# CC2640R2.net
KiCad netlist of a schematic drawn in Altium Designer
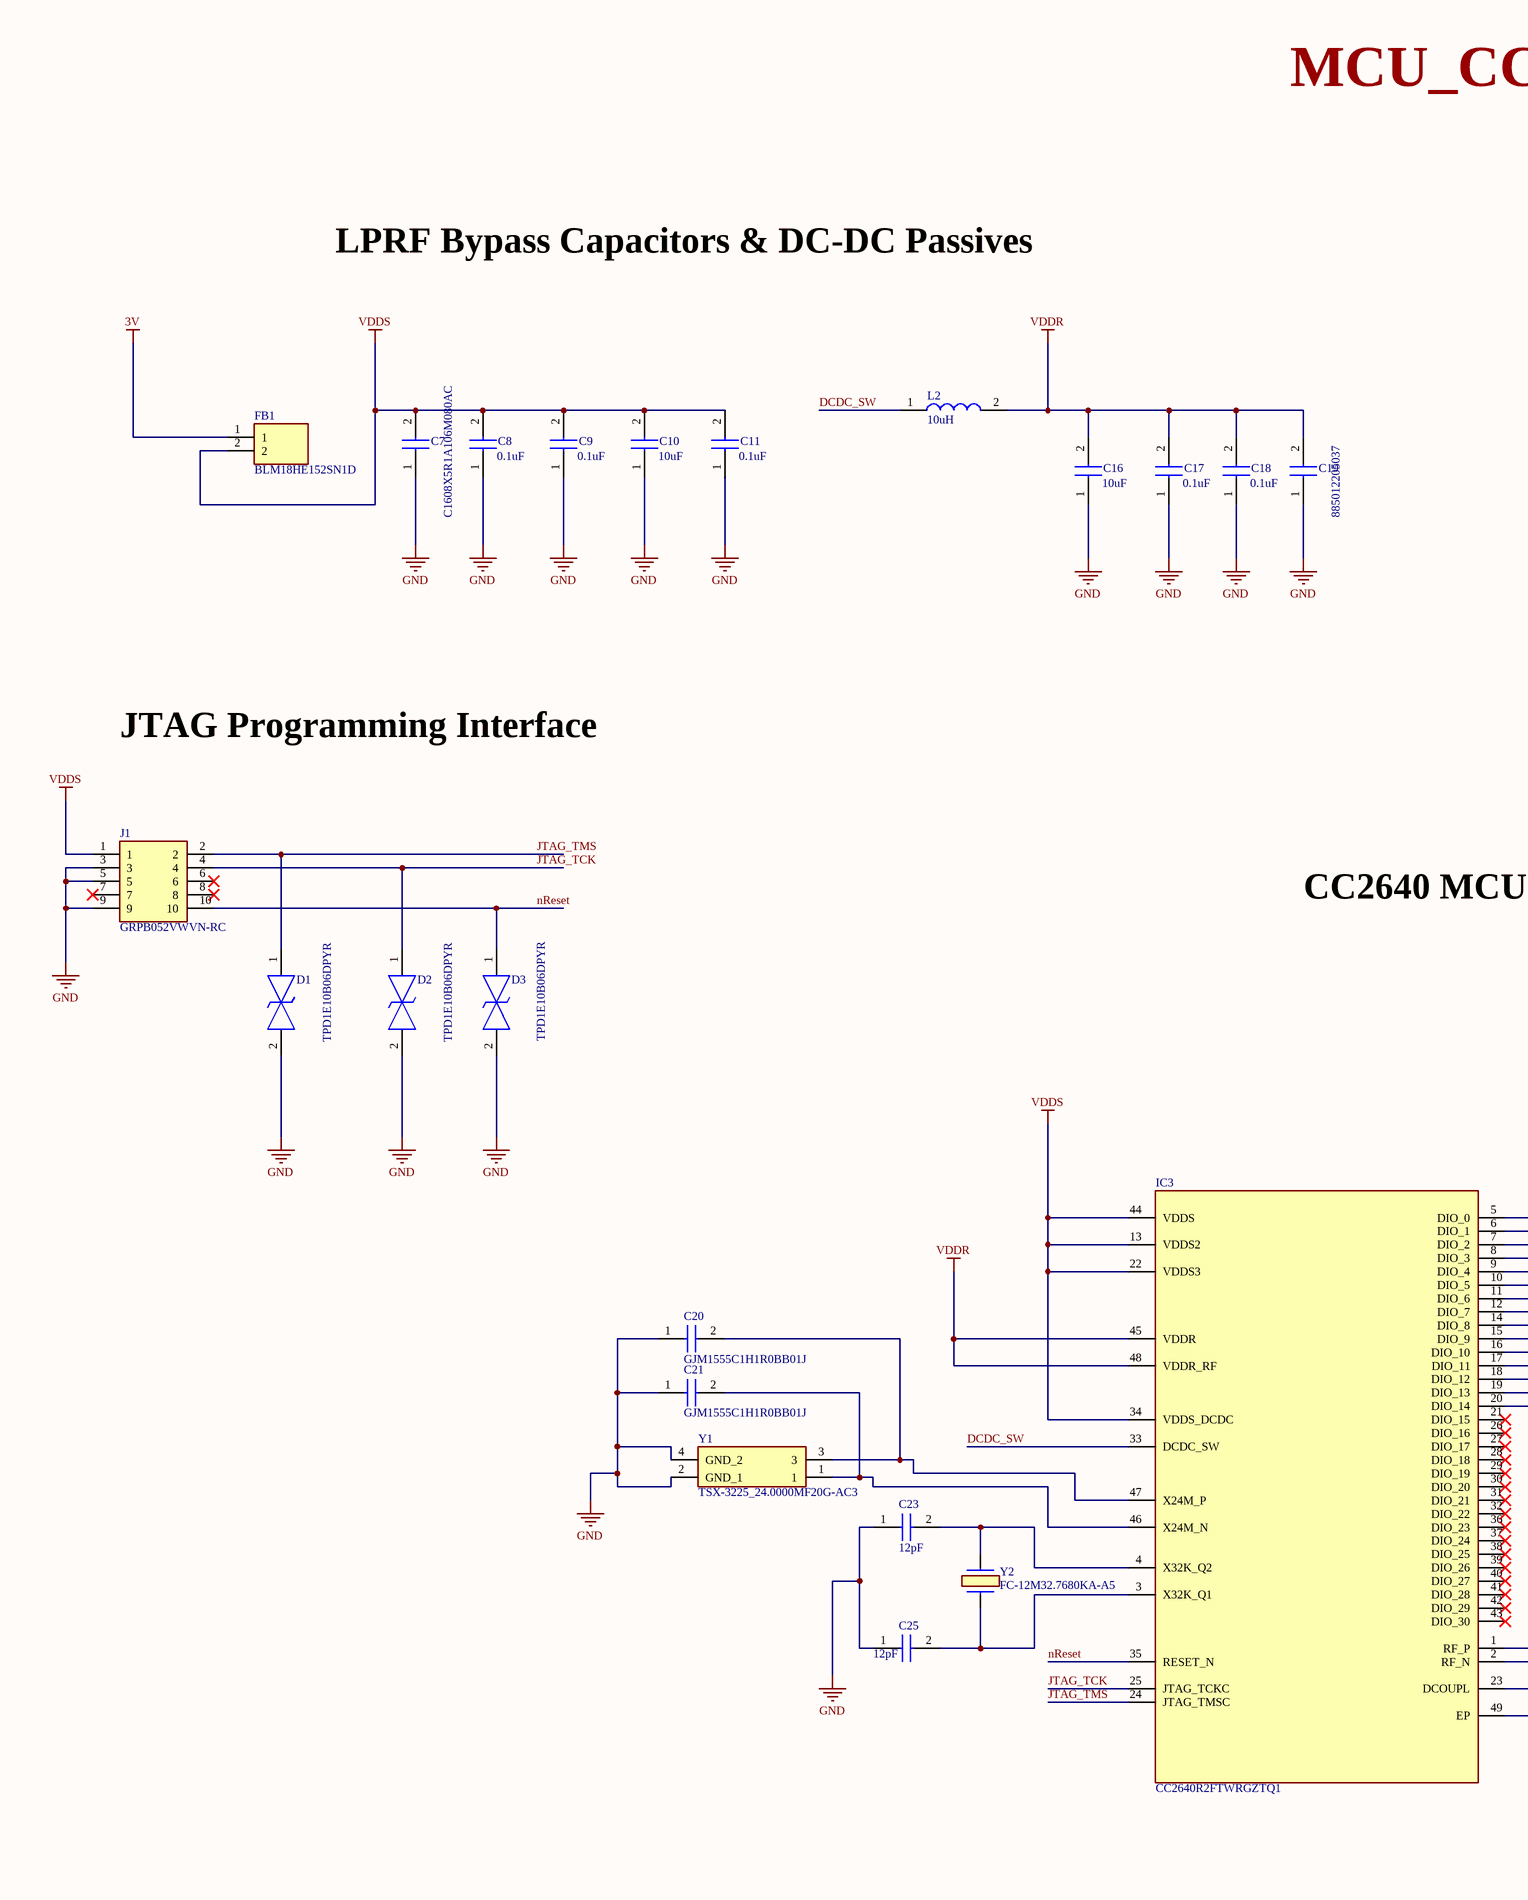
[diagram p0: CC2640R2.SchDoc, left]
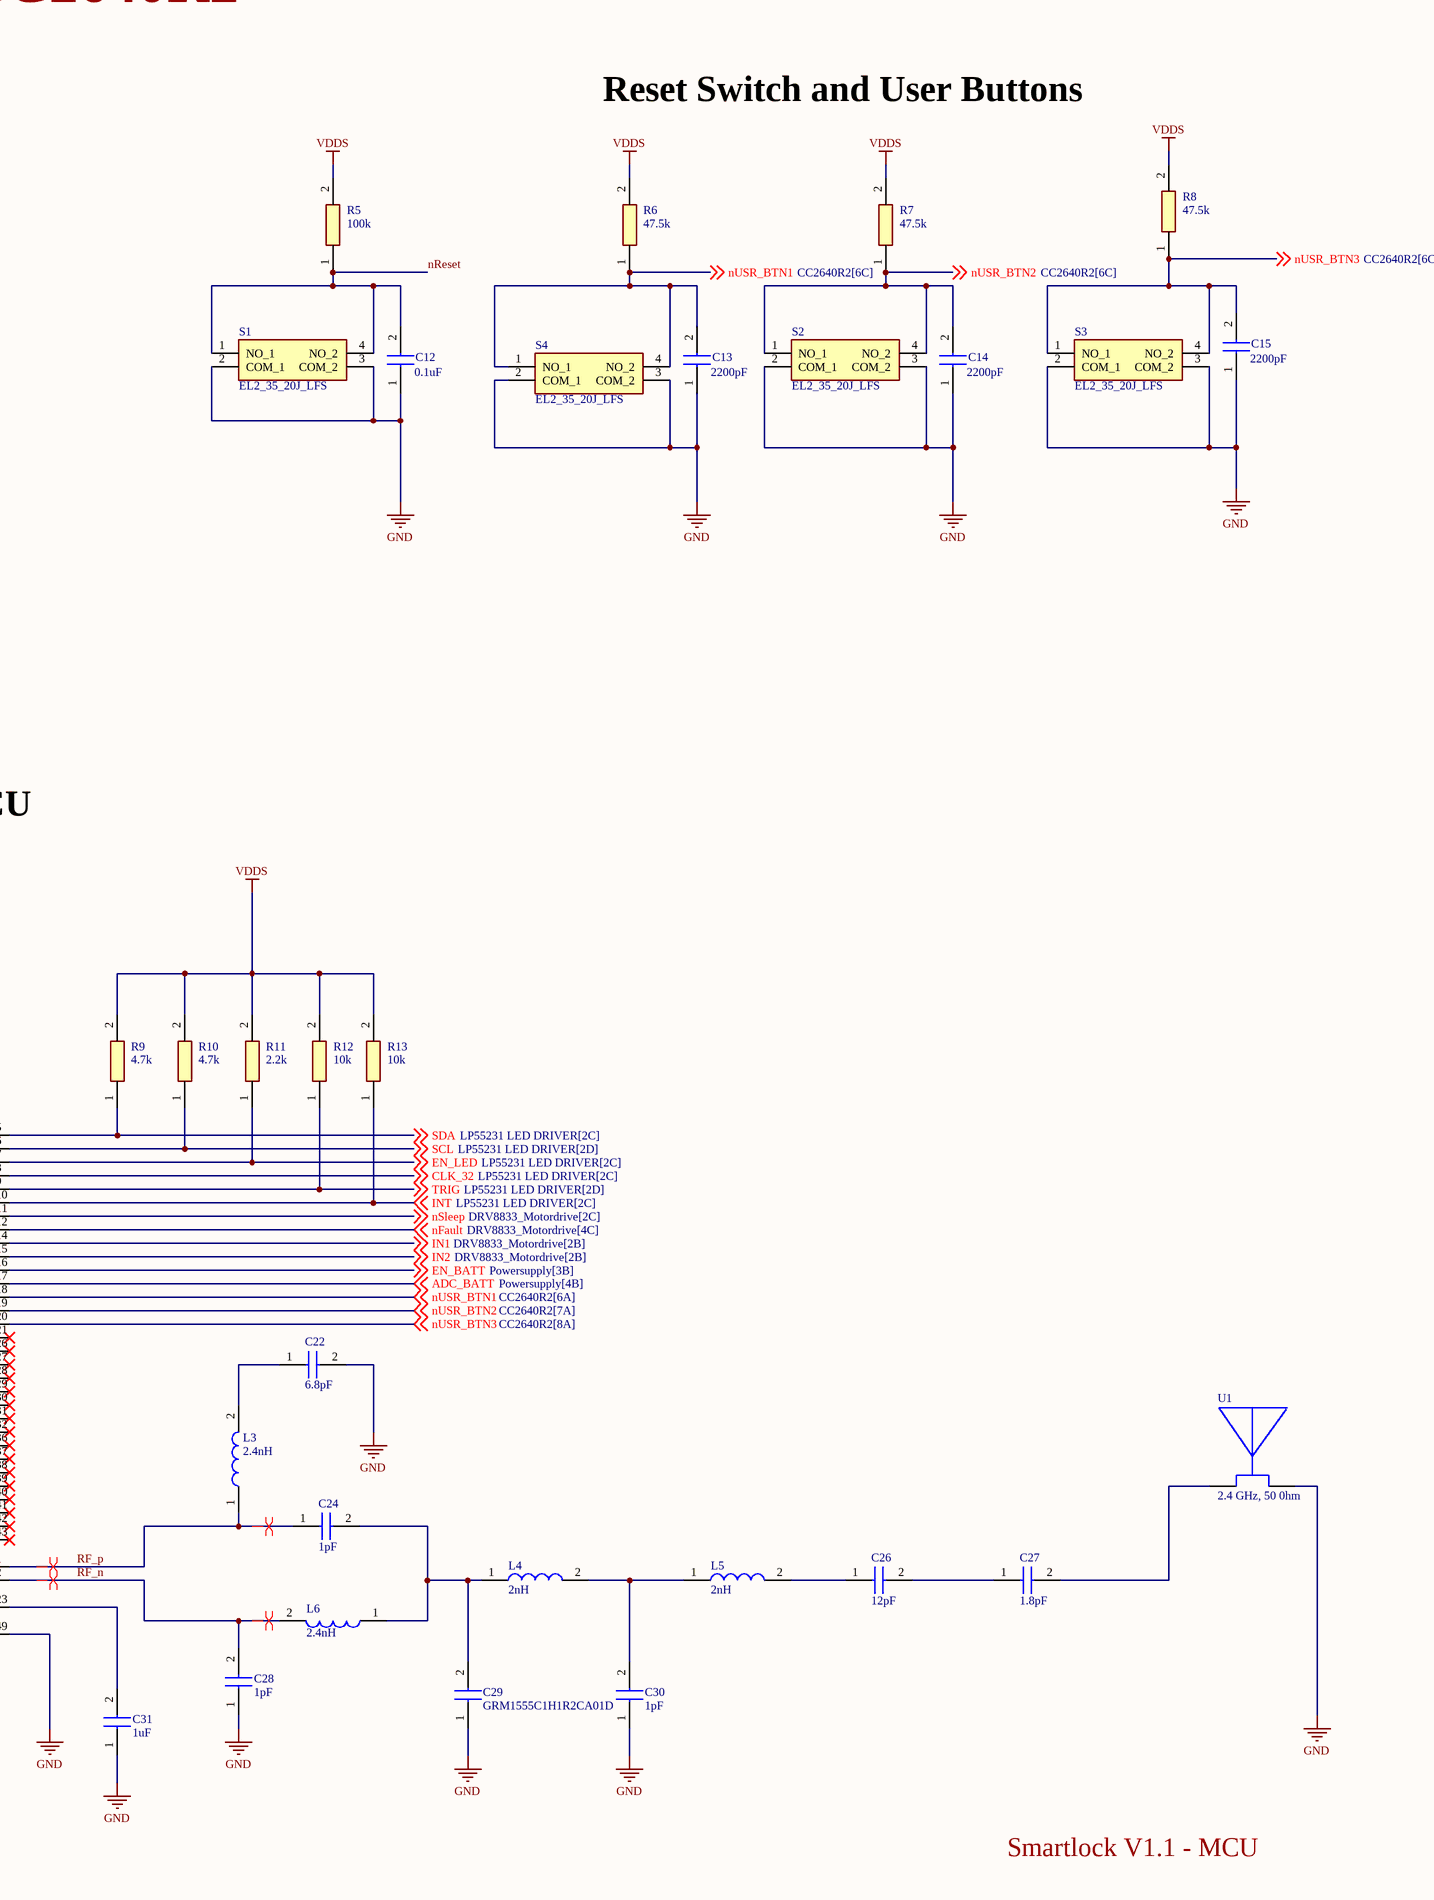
[diagram p1: CC2640R2.SchDoc, right]

(export (version "E")
  (design (tool "Eeschema 10.0.6"))
  (components
    (comp (ref "C7")
      (value "C1608X5R1A106M080AC")
      (footprint "Smart_lockV1.1:CAPC1608X80N")
      (description "Capacitor")
      (fields (field (name "MOUSER PART NUMBER") "810-C1608X5R1A106M"))
      (libsource (lib "*") (part "C1608X5R1A106M080AC"))
    )
    (comp (ref "C8")
      (value "0.1uF")
      (footprint "Smart_lockV1.1:CAPC1005X55N")
      (description "Capacitor,0.1uF 10V X7R")
      (fields
        (field (name "MANUFACTURER_PART_NUMBER") "GRM155R71A104KA01D")
        (field (name "MOUSER PART NUMBER") "81-GRM155R71A104KA1D")
      )
      (libsource (lib "*") (part "GRM155R71A104KA01D"))
    )
    (comp (ref "C9")
      (value "0.1uF")
      (footprint "Smart_lockV1.1:CAPC1005X55N")
      (description "Capacitor,0.1uF 10V X7R")
      (fields
        (field (name "MANUFACTURER_PART_NUMBER") "GRM155R71A104KA01D")
        (field (name "MOUSER PART NUMBER") "81-GRM155R71A104KA1D")
      )
      (libsource (lib "*") (part "GRM155R71A104KA01D"))
    )
    (comp (ref "C10")
      (value "10uF")
      (footprint "Smart_lockV1.1:CAPC2012X145N")
      (description "Capacitor,10uF 10V X7R")
      (fields
        (field (name "MANUFACTURER_PART_NUMBER") "GRM21BR71A106KE51L")
        (field (name "MOUSER PART NUMBER") "81-GRM21BR71A106KE51")
      )
      (libsource (lib "*") (part "GRM21BR71A106KE51L"))
    )
    (comp (ref "C11")
      (value "0.1uF")
      (footprint "Smart_lockV1.1:CAPC1005X55N")
      (description "Capacitor,01uF 10V X7R")
      (fields
        (field (name "MANUFACTURER_PART_NUMBER") "GRM155R71A104KA01D")
        (field (name "MOUSER PART NUMBER") "81-GRM155R71A104KA1D")
      )
      (libsource (lib "*") (part "GRM155R71A104KA01D"))
    )
    (comp (ref "C12")
      (value "0.1uF")
      (footprint "Smart_lockV1.1:CAPC1005X55N")
      (description "Capacitor 0.1uF 25V")
      (fields
        (field (name "MANUFACTURER_PART_NUMBER") "CGA2B3X7R1E104K050BB")
        (field (name "MOUSER PART NUMBER") "810-CGA2B3X7R1E104K")
      )
      (libsource (lib "*") (part "CGA2B3X7R1E104K050BB"))
    )
    (comp (ref "C13")
      (value "2200pF")
      (footprint "Smart_lockV1.1:CAPC1005X55N")
      (description "Capacitor 2200pF 50V")
      (fields
        (field (name "MANUFACTURER_PART_NUMBER") "C1005X7R1H222K050BA")
        (field (name "MOUSER PART NUMBER") "810-C1005X7R1H222K")
      )
      (libsource (lib "*") (part "C1005X7R1H222K050BA"))
    )
    (comp (ref "C14")
      (value "2200pF")
      (footprint "Smart_lockV1.1:CAPC1005X55N")
      (description "Capacitor")
      (fields
        (field (name "MANUFACTURER_PART_NUMBER") "C1005X7R1H222K050BA")
        (field (name "MOUSER PART NUMBER") "810-C1005X7R1H222K")
      )
      (libsource (lib "*") (part "C1005X7R1H222K050BA"))
    )
    (comp (ref "C15")
      (value "2200pF")
      (footprint "Smart_lockV1.1:CAPC1005X55N")
      (description "Capacitor")
      (fields
        (field (name "MANUFACTURER_PART_NUMBER") "C1005X7R1H222K050BA")
        (field (name "MOUSER PART NUMBER") "810-C1005X7R1H222K")
      )
      (libsource (lib "*") (part "C1005X7R1H222K050BA"))
    )
    (comp (ref "C16")
      (value "10uF")
      (footprint "Smart_lockV1.1:CAPC2012X145N")
      (description "Capacitor 10uF 10V X7R")
      (fields
        (field (name "MANUFACTURER_PART_NUMBER") "GRM21BR71A106KE51L")
        (field (name "MOUSER PART NUMBER") "81-GRM21BR71A106KE51")
      )
      (libsource (lib "*") (part "GRM21BR71A106KE51L"))
    )
    (comp (ref "C17")
      (value "0.1uF")
      (footprint "Smart_lockV1.1:CAPC1005X55N")
      (description "Capacitor 0.1uF 10V X7R")
      (fields
        (field (name "MANUFACTURER_PART_NUMBER") "GRM155R71A104KA01D")
        (field (name "MOUSER PART NUMBER") "81-GRM155R71A104KA1D")
      )
      (libsource (lib "*") (part "GRM155R71A104KA01D"))
    )
    (comp (ref "C18")
      (value "0.1uF")
      (footprint "Smart_lockV1.1:CAPC1005X55N")
      (description "Capacitor 0.1uF 10V X7R")
      (fields
        (field (name "MANUFACTURER_PART_NUMBER") "GRM155R71A104KA01D")
        (field (name "MOUSER PART NUMBER") "81-GRM155R71A104KA1D")
      )
      (libsource (lib "*") (part "GRM155R71A104KA01D"))
    )
    (comp (ref "C19")
      (value "885012205037")
      (footprint "Smart_lockV1.1:CAPC1005X55N")
      (description "Capacitor")
      (fields (field (name "MOUSER PART NUMBER") "710-885012205037"))
      (libsource (lib "*") (part "885012205037"))
    )
    (comp (ref "C20")
      (value "GJM1555C1H1R0BB01J")
      (footprint "Smart_lockV1.1:CAPC1005X55N")
      (description "Capacitor")
      (fields (field (name "MOUSER PART NUMBER") "81-GJM1555C1H1R0BB1J"))
      (libsource (lib "*") (part "GJM1555C1H1R0BB01J"))
    )
    (comp (ref "C21")
      (value "GJM1555C1H1R0BB01J")
      (footprint "Smart_lockV1.1:CAPC1005X55N")
      (description "Capacitor")
      (fields (field (name "MOUSER PART NUMBER") "81-GJM1555C1H1R0BB1J"))
      (libsource (lib "*") (part "GJM1555C1H1R0BB01J"))
    )
    (comp (ref "C22")
      (value "6.8pF")
      (footprint "Smart_lockV1.1:CAPC1005X55N")
      (description "6.8pF Capacitor 50V")
      (fields
        (field (name "MANUFACTURER_PART_NUMBER") "GRM1555C1H6R8CA01D")
        (field (name "MOUSER PART NUMBER") "81-GRM1555C1H6R8CA1D")
      )
      (libsource (lib "*") (part "GRM1555C1H6R8CA01D"))
    )
    (comp (ref "C23")
      (value "12pF")
      (footprint "Smart_lockV1.1:CAPC1005X55N")
      (description "Capacitor 12pF 50V")
      (fields
        (field (name "MANUFACTURER_PART_NUMBER") "GRM1555C1H120JA01D")
        (field (name "MOUSER PART NUMBER") "81-GRM1555C1H120JA1D")
      )
      (libsource (lib "*") (part "GRM1555C1H120JA01D"))
    )
    (comp (ref "C24")
      (value "1pF")
      (footprint "Smart_lockV1.1:CAPC1005X55N")
      (description "Capacitor 1pF 50V")
      (fields
        (field (name "MANUFACTURER_PART_NUMBER") "GJM1555C1H1R0BB01J")
        (field (name "MOUSER PART NUMBER") "81-GJM1555C1H1R0BB1J")
      )
      (libsource (lib "*") (part "GJM1555C1H1R0BB01J"))
    )
    (comp (ref "C25")
      (value "12pF")
      (footprint "Smart_lockV1.1:CAPC1005X55N")
      (description "Capacitor 12 pF 50V")
      (fields
        (field (name "MANUFACTURER_PART_NUMBER") "GRM1555C1H120JA01D")
        (field (name "MOUSER PART NUMBER") "81-GRM1555C1H120JA1D")
      )
      (libsource (lib "*") (part "GRM1555C1H120JA01D"))
    )
    (comp (ref "C26")
      (value "12pF")
      (footprint "Smart_lockV1.1:CAPC1005X55N")
      (description "Capacitor")
      (fields
        (field (name "MANUFACTURER_PART_NUMBER") "GRM1555C1H120JA01D")
        (field (name "MOUSER PART NUMBER") "81-GRM1555C1H120JA1D")
      )
      (libsource (lib "*") (part "GRM1555C1H120JA01D"))
    )
    (comp (ref "C27")
      (value "1.8pF")
      (footprint "Smart_lockV1.1:CAPC1005X55N")
      (description "Capacitor")
      (fields
        (field (name "MANUFACTURER_PART_NUMBER") "GRM1555C1H1R8CA01D")
        (field (name "MOUSER PART NUMBER") "81-GRM1555C1H1R8CA1D")
      )
      (libsource (lib "*") (part "GRM1555C1H1R8CA01D"))
    )
    (comp (ref "C28")
      (value "1pF")
      (footprint "Smart_lockV1.1:CAPC1005X55N")
      (description "Capacitor 1pF 5V")
      (fields
        (field (name "MANUFACTURER_PART_NUMBER") "GJM1555C1H1R0BB01J")
        (field (name "MOUSER PART NUMBER") "81-GJM1555C1H1R0BB1J")
      )
      (libsource (lib "*") (part "GJM1555C1H1R0BB01J"))
    )
    (comp (ref "C29")
      (value "GRM1555C1H1R2CA01D")
      (footprint "Smart_lockV1.1:CAPC1005X55N")
      (description "Capacitor")
      (fields (field (name "MOUSER PART NUMBER") "81-GRM1555C1H1R2CA1D"))
      (libsource (lib "*") (part "GRM1555C1H1R2CA01D"))
    )
    (comp (ref "C30")
      (value "1pF")
      (footprint "Smart_lockV1.1:CAPC1005X55N")
      (description "Capacitor 1pF")
      (fields
        (field (name "MANUFACTURER_PART_NUMBER") "GJM1555C1H1R0BB01J")
        (field (name "MOUSER PART NUMBER") "81-GJM1555C1H1R0BB1J")
      )
      (libsource (lib "*") (part "GJM1555C1H1R0BB01J"))
    )
    (comp (ref "C31")
      (value "1uF")
      (footprint "Smart_lockV1.1:CAPC1005X55N")
      (description "Capacitor 1uF 10V X5R")
      (fields
        (field (name "MANUFACTURER_PART_NUMBER") "GRM155R61A105KE15D")
        (field (name "MOUSER PART NUMBER") "81-GRM155R61A105KE15")
      )
      (libsource (lib "*") (part "GRM155R61A105KE15D"))
    )
    (comp (ref "D1")
      (value "TPD1E10B06DPYR")
      (footprint "Smart_lockV1.1:TPD1E10B06DPYR")
      (description "TVS Diode (Bi-directional)")
      (fields (field (name "MOUSER PART NUMBER") "595-TPD1E10B06DPYR"))
      (libsource (lib "*") (part "TPD1E10B06DPYR"))
    )
    (comp (ref "D2")
      (value "TPD1E10B06DPYR")
      (footprint "Smart_lockV1.1:TPD1E10B06DPYR")
      (description "TVS Diode (Bi-directional)")
      (fields (field (name "MOUSER PART NUMBER") "595-TPD1E10B06DPYR"))
      (libsource (lib "*") (part "TPD1E10B06DPYR"))
    )
    (comp (ref "D3")
      (value "TPD1E10B06DPYR")
      (footprint "Smart_lockV1.1:TPD1E10B06DPYR")
      (description "TVS Diode (Bi-directional)")
      (fields (field (name "MOUSER PART NUMBER") "595-TPD1E10B06DPYR"))
      (libsource (lib "*") (part "TPD1E10B06DPYR"))
    )
    (comp (ref "FB1")
      (value "BLM18HE152SN1D")
      (footprint "Smart_lockV1.1:BLM18SP221SN1B")
      (description "Ferrite Bead")
      (fields (field (name "MOUSER PART NUMBER") "81-BLM18HE152SN1D"))
      (libsource (lib "*") (part "BLM18HE152SN1D"))
    )
    (comp (ref "IC3")
      (value "CC2640R2FTWRGZTQ1")
      (footprint "QFN50P700X700X100-49N-D")
      (description "Integrated Circuit")
      (fields (field (name "MOUSER PART NUMBER") "595-2640R2FTWRGZTQ1"))
      (libsource (lib "Smart_lockV1.1") (part "CC2640R2FTWRGZTQ1"))
    )
    (comp (ref "J1")
      (value "GRPB052VWVN-RC")
      (footprint "Smart_lockV1.1:HDRV10W50P127_2X5_635X340X430P")
      (description "Connector")
      (libsource (lib "*") (part "GRPB052VWVN-RC"))
    )
    (comp (ref "L2")
      (value "10uH")
      (footprint "Smart_lockV1.1:INDC2112X145N")
      (description "Inductor,10uH")
      (fields
        (field (name "MANUFACTURER_PART_NUMBER") "CKS2125100M-T")
        (field (name "MOUSER PART NUMBER") "963-CKS2125100M-T")
      )
      (libsource (lib "*") (part "CKS2125100M-T"))
    )
    (comp (ref "L3")
      (value "2.4nH")
      (footprint "Smart_lockV1.1:LQG15WH0N7B02D")
      (description "Inductor 2.4 nH")
      (fields
        (field (name "MANUFACTURER_PART_NUMBER") "LQG15HN2N4S02D")
        (field (name "MOUSER PART NUMBER") "81-LQG15HN2N4S02D")
      )
      (libsource (lib "*") (part "LQG15HN2N4S02D"))
    )
    (comp (ref "L4")
      (value "2nH")
      (footprint "Smart_lockV1.1:LQG15WH0N7B02D")
      (description "Inductor")
      (fields
        (field (name "MANUFACTURER_PART_NUMBER") "LQG15HS2N0S02D")
        (field (name "MOUSER PART NUMBER") "81-LQG15HS2N0S02D")
      )
      (libsource (lib "*") (part "LQG15HS2N0S02D"))
    )
    (comp (ref "L5")
      (value "2nH")
      (footprint "Smart_lockV1.1:LQG15WH0N7B02D")
      (description "Inductor")
      (fields
        (field (name "MANUFACTURER_PART_NUMBER") "LQG15HS2N0S02D")
        (field (name "MOUSER PART NUMBER") "81-LQG15HS2N0S02D")
      )
      (libsource (lib "*") (part "LQG15HS2N0S02D"))
    )
    (comp (ref "L6")
      (value "2.4nH")
      (footprint "Smart_lockV1.1:LQG15WH0N7B02D")
      (description "Inductor")
      (fields
        (field (name "MANUFACTURER_PART_NUMBER") "LQG15HN2N4S02D")
        (field (name "MOUSER PART NUMBER") "81-LQG15HN2N4S02D")
      )
      (libsource (lib "*") (part "LQG15HN2N4S02D"))
    )
    (comp (ref "R5")
      (value "100k")
      (footprint "Smart_lockV1.1:RESC1005X35N")
      (description "Resistor")
      (fields
        (field (name "MANUFACTURER_PART_NUMBER") "RMCF0402FT100K")
        (field (name "MOUSER PART NUMBER") "708-RMCF0402FT100K")
      )
      (libsource (lib "*") (part "RMCF0402FT100K"))
    )
    (comp (ref "R6")
      (value "47.5k")
      (footprint "Smart_lockV1.1:RESC1005X40N")
      (description "Resistor")
      (fields
        (field (name "MANUFACTURER_PART_NUMBER") "CRCW040247K5FKED")
        (field (name "MOUSER PART NUMBER") "71-CRCW0402-47.5K-E3")
      )
      (libsource (lib "*") (part "CRCW040247K5FKED"))
    )
    (comp (ref "R7")
      (value "47.5k")
      (footprint "Smart_lockV1.1:RESC1005X40N")
      (description "Resistor")
      (fields
        (field (name "MANUFACTURER_PART_NUMBER") "CRCW040247K5FKED")
        (field (name "MOUSER PART NUMBER") "71-CRCW0402-47.5K-E3")
      )
      (libsource (lib "*") (part "CRCW040247K5FKED"))
    )
    (comp (ref "R8")
      (value "47.5k")
      (footprint "Smart_lockV1.1:RESC1005X40N")
      (description "Resistor")
      (fields
        (field (name "MANUFACTURER_PART_NUMBER") "CRCW040247K5FKED")
        (field (name "MOUSER PART NUMBER") "71-CRCW0402-47.5K-E3")
      )
      (libsource (lib "*") (part "CRCW040247K5FKED"))
    )
    (comp (ref "R9")
      (value "4.7k")
      (footprint "Smart_lockV1.1:ERJ3EKF1000V")
      (description "Resistor")
      (fields
        (field (name "MANUFACTURER_PART_NUMBER") "ERJ-3GEYJ472V")
        (field (name "MOUSER PART NUMBER") "667-ERJ-3GEYJ472V")
      )
      (libsource (lib "*") (part "ERJ-3GEYJ472V"))
    )
    (comp (ref "R10")
      (value "4.7k")
      (footprint "Smart_lockV1.1:ERJ3EKF1000V")
      (description "Resistor")
      (fields
        (field (name "MANUFACTURER_PART_NUMBER") "ERJ-3GEYJ472V")
        (field (name "MOUSER PART NUMBER") "667-ERJ-3GEYJ472V")
      )
      (libsource (lib "*") (part "ERJ-3GEYJ472V"))
    )
    (comp (ref "R11")
      (value "2.2k")
      (footprint "Smart_lockV1.1:RESC1608X55N")
      (description "Resistor")
      (fields
        (field (name "MANUFACTURER_PART_NUMBER") "RC0603FR-072K2L")
        (field (name "MOUSER PART NUMBER") "603-RC0603FR-072K2L")
      )
      (libsource (lib "*") (part "RC0603FR-072K2L"))
    )
    (comp (ref "R12")
      (value "10k")
      (footprint "Smart_lockV1.1:RESC1608X55N")
      (description "Resistor")
      (fields
        (field (name "MANUFACTURER_PART_NUMBER") "ERJ-3EKF1002V")
        (field (name "MOUSER PART NUMBER") "667-ERJ-3EKF1002V")
      )
      (libsource (lib "*") (part "ERJ-3EKF1002V"))
    )
    (comp (ref "R13")
      (value "10k")
      (footprint "Smart_lockV1.1:RESC1608X55N")
      (description "Resistor")
      (fields
        (field (name "MANUFACTURER_PART_NUMBER") "ERJ-3EKF1002V")
        (field (name "MOUSER PART NUMBER") "667-ERJ-3EKF1002V")
      )
      (libsource (lib "*") (part "ERJ-3EKF1002V"))
    )
    (comp (ref "S1")
      (value "EL2_35_20J_LFS")
      (footprint "Smart_lockV1.1:EL23520JLFS")
      (description "Switch")
      (fields (field (name "MANUFACTURER_PART_NUMBER") "EL2 35 20J LFS"))
      (libsource (lib "*") (part "EL2_35_20J_LFS"))
    )
    (comp (ref "S2")
      (value "EL2_35_20J_LFS")
      (footprint "Smart_lockV1.1:EL23520JLFS")
      (description "Switch")
      (fields (field (name "MANUFACTURER_PART_NUMBER") "EL2 35 20J LFS"))
      (libsource (lib "*") (part "EL2_35_20J_LFS"))
    )
    (comp (ref "S3")
      (value "EL2_35_20J_LFS")
      (footprint "Smart_lockV1.1:EL23520JLFS")
      (description "Switch")
      (fields (field (name "MANUFACTURER_PART_NUMBER") "EL2 35 20J LFS"))
      (libsource (lib "*") (part "EL2_35_20J_LFS"))
    )
    (comp (ref "S4")
      (value "EL2_35_20J_LFS")
      (footprint "Smart_lockV1.1:EL23520JLFS")
      (description "Switch")
      (fields (field (name "MANUFACTURER_PART_NUMBER") "EL2 35 20J LFS"))
      (libsource (lib "*") (part "EL2_35_20J_LFS"))
    )
    (comp (ref "U1")
      (value "2.4 GHz, 50 0hm")
      (footprint "ANT_IFA_USB_2_4GHZ_50R")
      (libsource (lib "Smart_lockV1.1") (part "2.4GHz Antenna"))
    )
    (comp (ref "Y1")
      (value "TSX-3225_24.0000MF20G-AC3")
      (footprint "Smart_lockV1.1:TSX-3225")
      (description "Crystal or Oscillator")
      (fields
        (field (name "MANUFACTURER_PART_NUMBER") "TSX-3225 24.0000MF20G-AC3")
        (field (name "MOUSER PART NUMBER") "732-TX325-24F20G-AC3")
      )
      (libsource (lib "Smart_lockV1.1") (part "TSX-3225_24.0000MF20G-AC3"))
    )
    (comp (ref "Y2")
      (value "FC-12M32.7680KA-A5")
      (footprint "FC12M327680KAA5")
      (description "Parallel - Fundamental Quartz Crystal, 0.032768MHz Nom")
      (fields (field (name "MANUFACTURER") "Epson"))
      (libsource (lib "Smart_lockV1.1") (part "FC-12M32.7680KA-A5"))
    )
  )
  (nets
    (net (code "1") (name "/DCDC_SW") (class "Default")
      (node (ref "IC3") (pin "33") (pinfunction "DCDC_SW_33") (pintype "passive"))
      (node (ref "L2") (pin "1") (pinfunction "1_1") (pintype "passive"))
    )
    (net (code "2") (name "/JTAG_TCK") (class "Default")
      (node (ref "D2") (pin "1") (pinfunction "1_1") (pintype "passive"))
      (node (ref "IC3") (pin "25") (pinfunction "JTAG_TCKC_25") (pintype "passive"))
      (node (ref "J1") (pin "4") (pinfunction "4_4") (pintype "passive"))
    )
    (net (code "3") (name "/JTAG_TMS") (class "Default")
      (node (ref "D1") (pin "1") (pinfunction "1_1") (pintype "passive"))
      (node (ref "IC3") (pin "24") (pinfunction "JTAG_TMSC_24") (pintype "passive"))
      (node (ref "J1") (pin "2") (pinfunction "2_2") (pintype "passive"))
    )
    (net (code "4") (name "/RF_n") (class "Default")
      (node (ref "C28") (pin "2") (pinfunction "2_2") (pintype "passive"))
      (node (ref "IC3") (pin "2") (pinfunction "RF_N_2") (pintype "passive"))
      (node (ref "L6") (pin "2") (pinfunction "2_2") (pintype "passive"))
    )
    (net (code "5") (name "/RF_p") (class "Default")
      (node (ref "C24") (pin "1") (pinfunction "1_1") (pintype "passive"))
      (node (ref "IC3") (pin "1") (pinfunction "RF_P_1") (pintype "passive"))
      (node (ref "L3") (pin "1") (pinfunction "1_1") (pintype "passive"))
    )
    (net (code "6") (name "/nReset") (class "Default")
      (node (ref "C12") (pin "2") (pinfunction "2_2") (pintype "passive"))
      (node (ref "D3") (pin "1") (pinfunction "1_1") (pintype "passive"))
      (node (ref "IC3") (pin "35") (pinfunction "RESET_N_35") (pintype "passive"))
      (node (ref "J1") (pin "10") (pinfunction "10_10") (pintype "passive"))
      (node (ref "R5") (pin "1") (pinfunction "1_1") (pintype "passive"))
      (node (ref "S1") (pin "1") (pinfunction "NO_1_1") (pintype "passive"))
      (node (ref "S1") (pin "4") (pinfunction "NO_2_4") (pintype "passive"))
    )
    (net (code "7") (name "3V") (class "Default")
      (node (ref "FB1") (pin "1") (pinfunction "1_1") (pintype "passive"))
    )
    (net (code "8") (name "ADC_BATT") (class "Default")
      (node (ref "IC3") (pin "17") (pinfunction "DIO_11_17") (pintype "passive"))
    )
    (net (code "9") (name "CLK_32") (class "Default")
      (node (ref "IC3") (pin "8") (pinfunction "DIO_3_8") (pintype "passive"))
    )
    (net (code "10") (name "EN_BATT") (class "Default")
      (node (ref "IC3") (pin "16") (pinfunction "DIO_10_16") (pintype "passive"))
    )
    (net (code "11") (name "EN_LED") (class "Default")
      (node (ref "IC3") (pin "7") (pinfunction "DIO_2_7") (pintype "passive"))
      (node (ref "R11") (pin "1") (pinfunction "1_1") (pintype "passive"))
    )
    (net (code "12") (name "GND") (class "Default")
      (node (ref "C10") (pin "1") (pinfunction "1_1") (pintype "passive"))
      (node (ref "C11") (pin "1") (pinfunction "1_1") (pintype "passive"))
      (node (ref "C12") (pin "1") (pinfunction "1_1") (pintype "passive"))
      (node (ref "C13") (pin "1") (pinfunction "1_1") (pintype "passive"))
      (node (ref "C14") (pin "1") (pinfunction "1_1") (pintype "passive"))
      (node (ref "C15") (pin "1") (pinfunction "1_1") (pintype "passive"))
      (node (ref "C16") (pin "1") (pinfunction "1_1") (pintype "passive"))
      (node (ref "C17") (pin "1") (pinfunction "1_1") (pintype "passive"))
      (node (ref "C18") (pin "1") (pinfunction "1_1") (pintype "passive"))
      (node (ref "C19") (pin "1") (pinfunction "1_1") (pintype "passive"))
      (node (ref "C20") (pin "1") (pinfunction "1_1") (pintype "passive"))
      (node (ref "C21") (pin "1") (pinfunction "1_1") (pintype "passive"))
      (node (ref "C22") (pin "2") (pinfunction "2_2") (pintype "passive"))
      (node (ref "C23") (pin "1") (pinfunction "1_1") (pintype "passive"))
      (node (ref "C25") (pin "1") (pinfunction "1_1") (pintype "passive"))
      (node (ref "C28") (pin "1") (pinfunction "1_1") (pintype "passive"))
      (node (ref "C29") (pin "1") (pinfunction "1_1") (pintype "passive"))
      (node (ref "C30") (pin "1") (pinfunction "1_1") (pintype "passive"))
      (node (ref "C31") (pin "1") (pinfunction "1_1") (pintype "passive"))
      (node (ref "C7") (pin "1") (pinfunction "1_1") (pintype "passive"))
      (node (ref "C8") (pin "1") (pinfunction "1_1") (pintype "passive"))
      (node (ref "C9") (pin "1") (pinfunction "1_1") (pintype "passive"))
      (node (ref "D1") (pin "2") (pinfunction "2_2") (pintype "passive"))
      (node (ref "D2") (pin "2") (pinfunction "2_2") (pintype "passive"))
      (node (ref "D3") (pin "2") (pinfunction "2_2") (pintype "passive"))
      (node (ref "IC3") (pin "49") (pinfunction "EP_49") (pintype "passive"))
      (node (ref "J1") (pin "3") (pinfunction "3_3") (pintype "passive"))
      (node (ref "J1") (pin "5") (pinfunction "5_5") (pintype "passive"))
      (node (ref "J1") (pin "9") (pinfunction "9_9") (pintype "passive"))
      (node (ref "S1") (pin "2") (pinfunction "COM_1_2") (pintype "passive"))
      (node (ref "S1") (pin "3") (pinfunction "COM_2_3") (pintype "passive"))
      (node (ref "S2") (pin "2") (pinfunction "COM_1_2") (pintype "passive"))
      (node (ref "S2") (pin "3") (pinfunction "COM_2_3") (pintype "passive"))
      (node (ref "S3") (pin "2") (pinfunction "COM_1_2") (pintype "passive"))
      (node (ref "S3") (pin "3") (pinfunction "COM_2_3") (pintype "passive"))
      (node (ref "S4") (pin "2") (pinfunction "COM_1_2") (pintype "passive"))
      (node (ref "S4") (pin "3") (pinfunction "COM_2_3") (pintype "passive"))
      (node (ref "U1") (pin "2") (pinfunction "GND_2") (pintype "passive"))
      (node (ref "Y1") (pin "2") (pinfunction "GND_1_2") (pintype "passive"))
      (node (ref "Y1") (pin "4") (pinfunction "GND_2_4") (pintype "passive"))
    )
    (net (code "13") (name "IN1") (class "Default")
      (node (ref "IC3") (pin "14") (pinfunction "DIO_8_14") (pintype "passive"))
    )
    (net (code "14") (name "IN2") (class "Default")
      (node (ref "IC3") (pin "15") (pinfunction "DIO_9_15") (pintype "passive"))
    )
    (net (code "15") (name "INT") (class "Default")
      (node (ref "IC3") (pin "10") (pinfunction "DIO_5_10") (pintype "passive"))
      (node (ref "R13") (pin "1") (pinfunction "1_1") (pintype "passive"))
    )
    (net (code "16") (name "Net-(C22-Pad1)") (class "Default")
      (node (ref "C22") (pin "1") (pinfunction "1_1") (pintype "passive"))
      (node (ref "L3") (pin "2") (pinfunction "2_2") (pintype "passive"))
    )
    (net (code "17") (name "Net-(C24-Pad2)") (class "Default")
      (node (ref "C24") (pin "2") (pinfunction "2_2") (pintype "passive"))
      (node (ref "C29") (pin "2") (pinfunction "2_2") (pintype "passive"))
      (node (ref "L4") (pin "1") (pinfunction "1_1") (pintype "passive"))
      (node (ref "L6") (pin "1") (pinfunction "1_1") (pintype "passive"))
    )
    (net (code "18") (name "Net-(C26-Pad1)") (class "Default")
      (node (ref "C26") (pin "1") (pinfunction "1_1") (pintype "passive"))
      (node (ref "L5") (pin "2") (pinfunction "2_2") (pintype "passive"))
    )
    (net (code "19") (name "Net-(C26-Pad2)") (class "Default")
      (node (ref "C26") (pin "2") (pinfunction "2_2") (pintype "passive"))
      (node (ref "C27") (pin "1") (pinfunction "1_1") (pintype "passive"))
    )
    (net (code "20") (name "Net-(C27-Pad2)") (class "Default")
      (node (ref "C27") (pin "2") (pinfunction "2_2") (pintype "passive"))
      (node (ref "U1") (pin "1") (pinfunction "1_1") (pintype "passive"))
    )
    (net (code "21") (name "Net-(C30-Pad2)") (class "Default")
      (node (ref "C30") (pin "2") (pinfunction "2_2") (pintype "passive"))
      (node (ref "L4") (pin "2") (pinfunction "2_2") (pintype "passive"))
      (node (ref "L5") (pin "1") (pinfunction "1_1") (pintype "passive"))
    )
    (net (code "22") (name "Net-(IC3-DCOUPL)") (class "Default")
      (node (ref "C31") (pin "2") (pinfunction "2_2") (pintype "passive"))
      (node (ref "IC3") (pin "23") (pinfunction "DCOUPL_23") (pintype "passive"))
    )
    (net (code "23") (name "Net-(IC3-X24M_N)") (class "Default")
      (node (ref "C21") (pin "2") (pinfunction "2_2") (pintype "passive"))
      (node (ref "IC3") (pin "46") (pinfunction "X24M_N_46") (pintype "passive"))
      (node (ref "Y1") (pin "1") (pinfunction "1_1") (pintype "passive"))
    )
    (net (code "24") (name "Net-(IC3-X24M_P)") (class "Default")
      (node (ref "C20") (pin "2") (pinfunction "2_2") (pintype "passive"))
      (node (ref "IC3") (pin "47") (pinfunction "X24M_P_47") (pintype "passive"))
      (node (ref "Y1") (pin "3") (pinfunction "3_3") (pintype "passive"))
    )
    (net (code "25") (name "Net-(IC3-X32K_Q1)") (class "Default")
      (node (ref "C25") (pin "2") (pinfunction "2_2") (pintype "passive"))
      (node (ref "IC3") (pin "3") (pinfunction "X32K_Q1_3") (pintype "passive"))
      (node (ref "Y2") (pin "2") (pinfunction "2_2") (pintype "passive"))
    )
    (net (code "26") (name "Net-(IC3-X32K_Q2)") (class "Default")
      (node (ref "C23") (pin "2") (pinfunction "2_2") (pintype "passive"))
      (node (ref "IC3") (pin "4") (pinfunction "X32K_Q2_4") (pintype "passive"))
      (node (ref "Y2") (pin "1") (pinfunction "1_1") (pintype "passive"))
    )
    (net (code "27") (name "SCL") (class "Default")
      (node (ref "IC3") (pin "6") (pinfunction "DIO_1_6") (pintype "passive"))
      (node (ref "R10") (pin "1") (pinfunction "1_1") (pintype "passive"))
    )
    (net (code "28") (name "SDA") (class "Default")
      (node (ref "IC3") (pin "5") (pinfunction "DIO_0_5") (pintype "passive"))
      (node (ref "R9") (pin "1") (pinfunction "1_1") (pintype "passive"))
    )
    (net (code "29") (name "TRIG") (class "Default")
      (node (ref "IC3") (pin "9") (pinfunction "DIO_4_9") (pintype "passive"))
      (node (ref "R12") (pin "1") (pinfunction "1_1") (pintype "passive"))
    )
    (net (code "30") (name "VDDR") (class "Default")
      (node (ref "C16") (pin "2") (pinfunction "2_2") (pintype "passive"))
      (node (ref "C17") (pin "2") (pinfunction "2_2") (pintype "passive"))
      (node (ref "C18") (pin "2") (pinfunction "2_2") (pintype "passive"))
      (node (ref "C19") (pin "2") (pinfunction "2_2") (pintype "passive"))
      (node (ref "IC3") (pin "45") (pinfunction "VDDR_45") (pintype "passive"))
      (node (ref "IC3") (pin "48") (pinfunction "VDDR_RF_48") (pintype "passive"))
      (node (ref "L2") (pin "2") (pinfunction "2_2") (pintype "passive"))
    )
    (net (code "31") (name "VDDS") (class "Default")
      (node (ref "C10") (pin "2") (pinfunction "2_2") (pintype "passive"))
      (node (ref "C11") (pin "2") (pinfunction "2_2") (pintype "passive"))
      (node (ref "C7") (pin "2") (pinfunction "2_2") (pintype "passive"))
      (node (ref "C8") (pin "2") (pinfunction "2_2") (pintype "passive"))
      (node (ref "C9") (pin "2") (pinfunction "2_2") (pintype "passive"))
      (node (ref "FB1") (pin "2") (pinfunction "2_2") (pintype "passive"))
      (node (ref "IC3") (pin "13") (pinfunction "VDDS2_13") (pintype "passive"))
      (node (ref "IC3") (pin "22") (pinfunction "VDDS3_22") (pintype "passive"))
      (node (ref "IC3") (pin "34") (pinfunction "VDDS_DCDC_34") (pintype "passive"))
      (node (ref "IC3") (pin "44") (pinfunction "VDDS_44") (pintype "passive"))
      (node (ref "J1") (pin "1") (pinfunction "1_1") (pintype "passive"))
      (node (ref "R10") (pin "2") (pinfunction "2_2") (pintype "passive"))
      (node (ref "R11") (pin "2") (pinfunction "2_2") (pintype "passive"))
      (node (ref "R12") (pin "2") (pinfunction "2_2") (pintype "passive"))
      (node (ref "R13") (pin "2") (pinfunction "2_2") (pintype "passive"))
      (node (ref "R5") (pin "2") (pinfunction "2_2") (pintype "passive"))
      (node (ref "R6") (pin "2") (pinfunction "2_2") (pintype "passive"))
      (node (ref "R7") (pin "2") (pinfunction "2_2") (pintype "passive"))
      (node (ref "R8") (pin "2") (pinfunction "2_2") (pintype "passive"))
      (node (ref "R9") (pin "2") (pinfunction "2_2") (pintype "passive"))
    )
    (net (code "32") (name "nFault") (class "Default")
      (node (ref "IC3") (pin "12") (pinfunction "DIO_7_12") (pintype "passive"))
    )
    (net (code "33") (name "nSleep") (class "Default")
      (node (ref "IC3") (pin "11") (pinfunction "DIO_6_11") (pintype "passive"))
    )
    (net (code "34") (name "nUSR_BTN1") (class "Default")
      (node (ref "C13") (pin "2") (pinfunction "2_2") (pintype "passive"))
      (node (ref "IC3") (pin "18") (pinfunction "DIO_12_18") (pintype "passive"))
      (node (ref "R6") (pin "1") (pinfunction "1_1") (pintype "passive"))
      (node (ref "S4") (pin "1") (pinfunction "NO_1_1") (pintype "passive"))
      (node (ref "S4") (pin "4") (pinfunction "NO_2_4") (pintype "passive"))
    )
    (net (code "35") (name "nUSR_BTN2") (class "Default")
      (node (ref "C14") (pin "2") (pinfunction "2_2") (pintype "passive"))
      (node (ref "IC3") (pin "19") (pinfunction "DIO_13_19") (pintype "passive"))
      (node (ref "R7") (pin "1") (pinfunction "1_1") (pintype "passive"))
      (node (ref "S2") (pin "1") (pinfunction "NO_1_1") (pintype "passive"))
      (node (ref "S2") (pin "4") (pinfunction "NO_2_4") (pintype "passive"))
    )
    (net (code "36") (name "nUSR_BTN3") (class "Default")
      (node (ref "C15") (pin "2") (pinfunction "2_2") (pintype "passive"))
      (node (ref "IC3") (pin "20") (pinfunction "DIO_14_20") (pintype "passive"))
      (node (ref "R8") (pin "1") (pinfunction "1_1") (pintype "passive"))
      (node (ref "S3") (pin "1") (pinfunction "NO_1_1") (pintype "passive"))
      (node (ref "S3") (pin "4") (pinfunction "NO_2_4") (pintype "passive"))
    )
    (net (code "37") (name "unconnected-(IC3-DIO_15-Pad21)") (class "Default")
      (node (ref "IC3") (pin "21") (pinfunction "DIO_15_21") (pintype "passive+no_connect"))
    )
    (net (code "38") (name "unconnected-(IC3-DIO_16-Pad26)") (class "Default")
      (node (ref "IC3") (pin "26") (pinfunction "DIO_16_26") (pintype "passive+no_connect"))
    )
    (net (code "39") (name "unconnected-(IC3-DIO_17-Pad27)") (class "Default")
      (node (ref "IC3") (pin "27") (pinfunction "DIO_17_27") (pintype "passive+no_connect"))
    )
    (net (code "40") (name "unconnected-(IC3-DIO_18-Pad28)") (class "Default")
      (node (ref "IC3") (pin "28") (pinfunction "DIO_18_28") (pintype "passive+no_connect"))
    )
    (net (code "41") (name "unconnected-(IC3-DIO_19-Pad29)") (class "Default")
      (node (ref "IC3") (pin "29") (pinfunction "DIO_19_29") (pintype "passive+no_connect"))
    )
    (net (code "42") (name "unconnected-(IC3-DIO_20-Pad30)") (class "Default")
      (node (ref "IC3") (pin "30") (pinfunction "DIO_20_30") (pintype "passive+no_connect"))
    )
    (net (code "43") (name "unconnected-(IC3-DIO_21-Pad31)") (class "Default")
      (node (ref "IC3") (pin "31") (pinfunction "DIO_21_31") (pintype "passive+no_connect"))
    )
    (net (code "44") (name "unconnected-(IC3-DIO_22-Pad32)") (class "Default")
      (node (ref "IC3") (pin "32") (pinfunction "DIO_22_32") (pintype "passive+no_connect"))
    )
    (net (code "45") (name "unconnected-(IC3-DIO_23-Pad36)") (class "Default")
      (node (ref "IC3") (pin "36") (pinfunction "DIO_23_36") (pintype "passive+no_connect"))
    )
    (net (code "46") (name "unconnected-(IC3-DIO_24-Pad37)") (class "Default")
      (node (ref "IC3") (pin "37") (pinfunction "DIO_24_37") (pintype "passive+no_connect"))
    )
    (net (code "47") (name "unconnected-(IC3-DIO_25-Pad38)") (class "Default")
      (node (ref "IC3") (pin "38") (pinfunction "DIO_25_38") (pintype "passive+no_connect"))
    )
    (net (code "48") (name "unconnected-(IC3-DIO_26-Pad39)") (class "Default")
      (node (ref "IC3") (pin "39") (pinfunction "DIO_26_39") (pintype "passive+no_connect"))
    )
    (net (code "49") (name "unconnected-(IC3-DIO_27-Pad40)") (class "Default")
      (node (ref "IC3") (pin "40") (pinfunction "DIO_27_40") (pintype "passive+no_connect"))
    )
    (net (code "50") (name "unconnected-(IC3-DIO_28-Pad41)") (class "Default")
      (node (ref "IC3") (pin "41") (pinfunction "DIO_28_41") (pintype "passive+no_connect"))
    )
    (net (code "51") (name "unconnected-(IC3-DIO_29-Pad42)") (class "Default")
      (node (ref "IC3") (pin "42") (pinfunction "DIO_29_42") (pintype "passive+no_connect"))
    )
    (net (code "52") (name "unconnected-(IC3-DIO_30-Pad43)") (class "Default")
      (node (ref "IC3") (pin "43") (pinfunction "DIO_30_43") (pintype "passive+no_connect"))
    )
    (net (code "53") (name "unconnected-(J1-Pad6)") (class "Default")
      (node (ref "J1") (pin "6") (pinfunction "6_6") (pintype "passive+no_connect"))
    )
    (net (code "54") (name "unconnected-(J1-Pad7)") (class "Default")
      (node (ref "J1") (pin "7") (pinfunction "7_7") (pintype "passive+no_connect"))
    )
    (net (code "55") (name "unconnected-(J1-Pad8)") (class "Default")
      (node (ref "J1") (pin "8") (pinfunction "8_8") (pintype "passive+no_connect"))
    )
  )
)
